# avr.net
KiCad netlist of a schematic drawn in Altium Designer
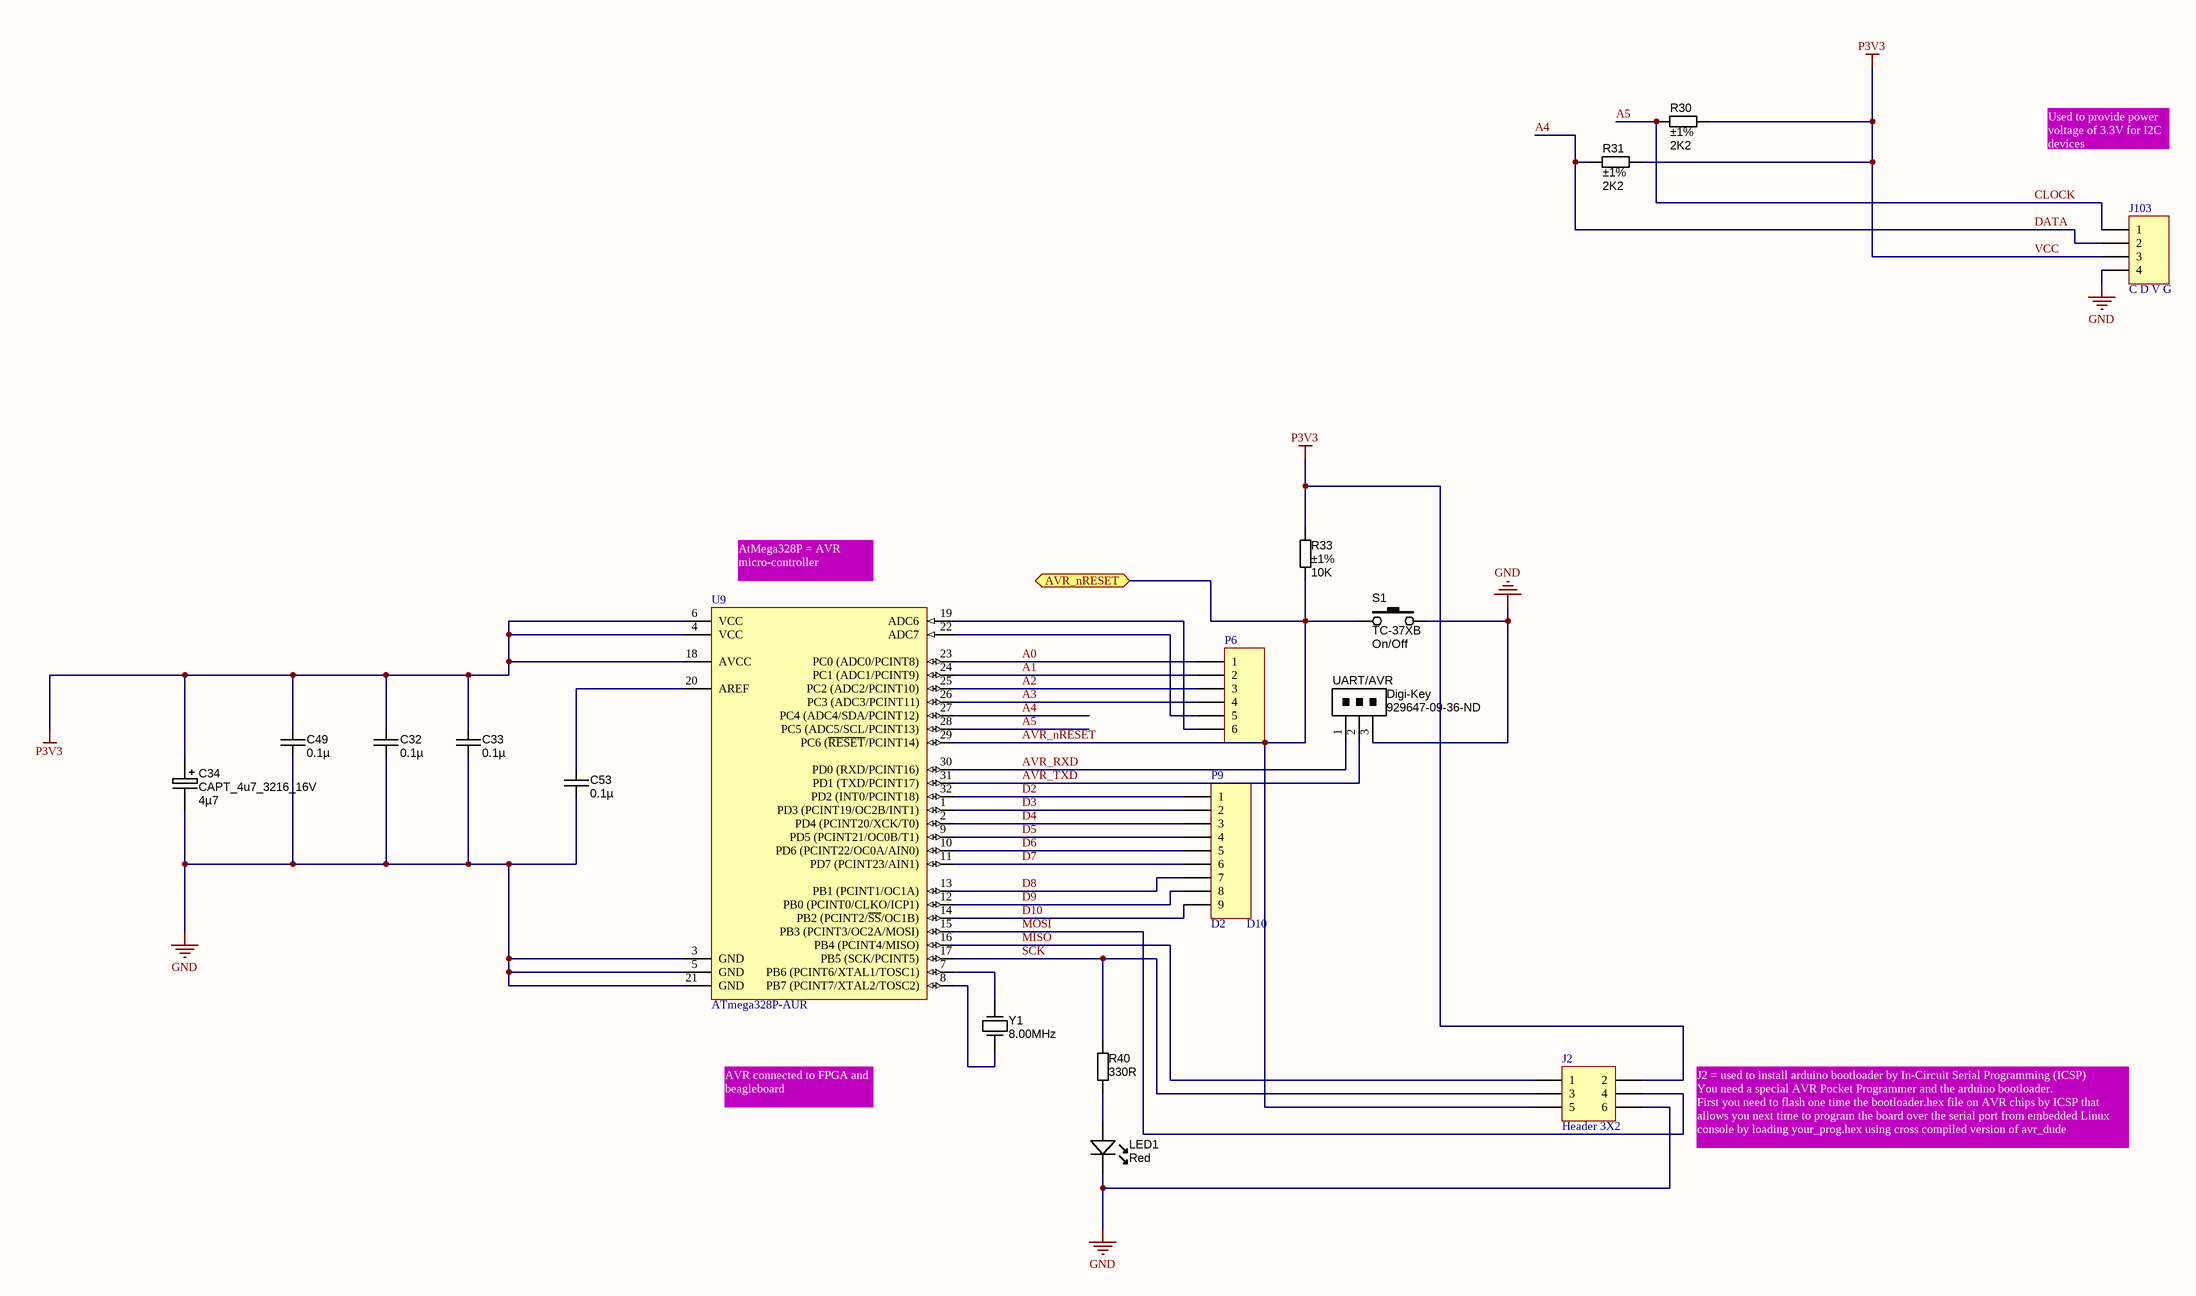
[diagram p0: avr.SchDoc]

(export (version "E")
  (design (tool "Eeschema 10.0.6"))
  (components
    (comp (ref "C32")
      (value "0.1µ")
      (footprint "CAPC1005X55N")
      (description "Capacitor SMD Cer 1uF 10% 16V X5R 0402")
      (fields (field (name "TOLERANCE") "±10%"))
      (libsource (lib "PBL - Capacitors") (part "CAPC_1u_0402_X5R_6V3_10%"))
    )
    (comp (ref "C33")
      (value "0.1µ")
      (footprint "CAPC1005X55N")
      (description "Capacitor SMD Cer 1uF 10% 16V X5R 0402")
      (fields (field (name "TOLERANCE") "±10%"))
      (libsource (lib "PBL - Capacitors") (part "CAPC_1u_0402_X5R_6V3_10%"))
    )
    (comp (ref "C34")
      (value "CAPT_4u7_3216_16V")
      (footprint "CAPMP3216X180N")
      (description "Capacitor SMD Tantalum 4.7uF 10% 16V 3216-18")
      (fields (field (name "ALTIUM_VALUE") "4µ7") (field (name "TOLERANCE") "±10%"))
      (libsource (lib "PBL - Capacitors") (part "CAPT_4u7_3216_16V"))
    )
    (comp (ref "C49")
      (value "0.1µ")
      (footprint "CAPC1005X55N")
      (description "Capacitor SMD Cer 1uF 10% 16V X5R 0402")
      (fields (field (name "TOLERANCE") "±10%"))
      (libsource (lib "PBL - Capacitors") (part "CAPC_1u_0402_X5R_6V3_10%"))
    )
    (comp (ref "C53")
      (value "0.1µ")
      (footprint "CAPC1005X55N")
      (description "Capacitor SMD Cer 1uF 10% 16V X5R 0402")
      (fields (field (name "TOLERANCE") "±10%"))
      (libsource (lib "PBL - Capacitors") (part "CAPC_1u_0402_X5R_6V3_10%"))
    )
    (comp (ref "J2")
      (value "Header 3X2")
      (footprint "HDR2X3")
      (description "Header, 3-Pin, Dual row")
      (fields (field (name "PUBLISHER") "Altium Limited"))
      (libsource (lib "Miscellaneous Connectors") (part "Header 3X2"))
    )
    (comp (ref "J103")
      (value "C D V G")
      (footprint "HDR1X4")
      (description "Header, 4-Pin")
      (fields (field (name "PUBLISHER") "Altium Limited"))
      (libsource (lib "Miscellaneous Connectors") (part "Header 4"))
    )
    (comp (ref "LED1")
      (value "~")
      (footprint "LED-0603-RED")
      (description "LED 0805 SMD Red 6mcd 621nm")
      (fields (field (name "COLOR") "Red"))
      (libsource (lib "PBL - Light Sources") (part "LED_SMD_Red_0805_6mcd"))
    )
    (comp (ref "P6")
      (value "~")
      (footprint "HDR1X6")
      (description "Header, 6-Pin")
      (fields (field (name "PUBLISHER") "Altium Limited"))
      (libsource (lib "Miscellaneous Connectors") (part "Header 6"))
    )
    (comp (ref "P9")
      (value "D2       D10")
      (footprint "HDR1X9")
      (description "Header, 9-Pin")
      (fields (field (name "PUBLISHER") "Altium Limited"))
      (libsource (lib "Miscellaneous Connectors") (part "Header 9"))
    )
    (comp (ref "R30")
      (value "2K2")
      (footprint "RESC1005N")
      (description "Resistor SMD chip 2.2k Ohm 0.125W 1% 0805")
      (fields (field (name "TOLERANCE") "±1%") (field (name "Comment") "Thick Film"))
      (libsource (lib "PBL - Resistors") (part "RES_2K2_0805_1%"))
    )
    (comp (ref "R31")
      (value "2K2")
      (footprint "RESC1005N")
      (description "Resistor SMD chip 2.2k Ohm 0.125W 1% 0805")
      (fields (field (name "TOLERANCE") "±1%") (field (name "Comment") "Thick Film"))
      (libsource (lib "PBL - Resistors") (part "RES_2K2_0805_1%"))
    )
    (comp (ref "R33")
      (value "10K")
      (footprint "RESC1005X40N")
      (description "Resistor SMD chip 10k Ohm 0.063W 1% 0402")
      (fields (field (name "TOLERANCE") "±1%") (field (name "Comment") "Thick Film"))
      (libsource (lib "PBL - Resistors") (part "RES_10K_0402_1%"))
    )
    (comp (ref "R40")
      (value "330R")
      (footprint "RESC1005X40N")
      (description "Resistor SMD chip 330 Ohm 0.063W 5% 0402")
      (fields (field (name "TOLERANCE") "±5%") (field (name "Comment") "Thick Film"))
      (libsource (lib "PBL - Resistors") (part "RES_330R_0402_5%"))
    )
    (comp (ref "S1")
      (value "SW_THT_PB_5.0mm")
      (footprint "TACT-SWITCH-TS1143")
      (description "Switch, tact, 5.0mm stem")
      (fields (field (name "MANUFACTURER PART NUMBER 1") "TC-37XB") (field (name "FUNCTION") "On/Off"))
      (libsource (lib "PBL - Switches") (part "SW_THT_PB_5.0mm"))
    )
    (comp (ref "U9")
      (value "ATmega328P-AUR")
      (footprint "32A_N")
      (fields (field (name "PUBLISHER") "Altium Limited"))
      (libsource (lib "Atmel Microcontroller 8-Bit megaAVR") (part "ATmega328-AUR"))
    )
    (comp (ref "UART/AVR")
      (value "R T G")
      (footprint "1x3POS_HEADER")
      (description "Pin Header, THT, Single-row, 2.54mm pitch")
      (fields
        (field (name "SUPPLIER 1") "Digi-Key")
        (field (name "SUPPLIER PART NUMBER 1") "929647-09-36-ND")
      )
      (libsource (lib "PBL - Connectors") (part "CONN_HEADER_1x3P_0.100in"))
    )
    (comp (ref "Y1")
      (value "8.00MHz")
      (footprint "CRYSTAL_HC49-US-SM")
      (description "Resonator Ceramic 8.00 MHz 30ppm")
      (libsource (lib "PBL - Resonators") (part "Crystal_6MHz_HC49/US"))
    )
  )
  (nets
    (net (code "1") (name "/A0") (class "Default")
      (node (ref "P6") (pin "1") (pinfunction "1_1") (pintype "passive"))
      (node (ref "U9") (pin "23") (pinfunction "PC0_(ADC0/PCINT8)_23") (pintype "bidirectional"))
    )
    (net (code "2") (name "/A1") (class "Default")
      (node (ref "P6") (pin "2") (pinfunction "2_2") (pintype "passive"))
      (node (ref "U9") (pin "24") (pinfunction "PC1_(ADC1/PCINT9)_24") (pintype "bidirectional"))
    )
    (net (code "3") (name "/A2") (class "Default")
      (node (ref "P6") (pin "3") (pinfunction "3_3") (pintype "passive"))
      (node (ref "U9") (pin "25") (pinfunction "PC2_(ADC2/PCINT10)_25") (pintype "bidirectional"))
    )
    (net (code "4") (name "/A3") (class "Default")
      (node (ref "P6") (pin "4") (pinfunction "4_4") (pintype "passive"))
      (node (ref "U9") (pin "26") (pinfunction "PC3_(ADC3/PCINT11)_26") (pintype "bidirectional"))
    )
    (net (code "5") (name "/A4") (class "Default")
      (node (ref "J103") (pin "2") (pinfunction "2_2") (pintype "passive"))
      (node (ref "R31") (pin "1") (pinfunction "1_1") (pintype "passive"))
      (node (ref "U9") (pin "27") (pinfunction "PC4_(ADC4/SDA/PCINT12)_27") (pintype "bidirectional"))
    )
    (net (code "6") (name "/A5") (class "Default")
      (node (ref "J103") (pin "1") (pinfunction "1_1") (pintype "passive"))
      (node (ref "R30") (pin "1") (pinfunction "1_1") (pintype "passive"))
      (node (ref "U9") (pin "28") (pinfunction "PC5_(ADC5/SCL/PCINT13)_28") (pintype "bidirectional"))
    )
    (net (code "7") (name "/AVR_RXD") (class "Default")
      (node (ref "U9") (pin "30") (pinfunction "PD0_(RXD/PCINT16)_30") (pintype "bidirectional"))
      (node (ref "UART/AVR") (pin "1") (pinfunction "1_1") (pintype "passive"))
    )
    (net (code "8") (name "/AVR_TXD") (class "Default")
      (node (ref "U9") (pin "31") (pinfunction "PD1_(TXD/PCINT17)_31") (pintype "bidirectional"))
      (node (ref "UART/AVR") (pin "2") (pinfunction "2_2") (pintype "passive"))
    )
    (net (code "9") (name "/AVR_nRESET") (class "Default")
      (node (ref "J2") (pin "5") (pinfunction "5_5") (pintype "passive"))
      (node (ref "R33") (pin "2") (pinfunction "2_2") (pintype "passive"))
      (node (ref "S1") (pin "1") (pintype "passive"))
      (node (ref "U9") (pin "29") (pinfunction "PC6_(~{RESET}/PCINT14)_29") (pintype "bidirectional"))
    )
    (net (code "10") (name "/D2") (class "Default")
      (node (ref "P9") (pin "1") (pinfunction "1_1") (pintype "passive"))
      (node (ref "U9") (pin "32") (pinfunction "PD2_(INT0/PCINT18)_32") (pintype "bidirectional"))
    )
    (net (code "11") (name "/D3") (class "Default")
      (node (ref "P9") (pin "2") (pinfunction "2_2") (pintype "passive"))
      (node (ref "U9") (pin "1") (pinfunction "PD3_(PCINT19/OC2B/INT1)_1") (pintype "bidirectional"))
    )
    (net (code "12") (name "/D4") (class "Default")
      (node (ref "P9") (pin "3") (pinfunction "3_3") (pintype "passive"))
      (node (ref "U9") (pin "2") (pinfunction "PD4_(PCINT20/XCK/T0)_2") (pintype "bidirectional"))
    )
    (net (code "13") (name "/D5") (class "Default")
      (node (ref "P9") (pin "4") (pinfunction "4_4") (pintype "passive"))
      (node (ref "U9") (pin "9") (pinfunction "PD5_(PCINT21/OC0B/T1)_9") (pintype "bidirectional"))
    )
    (net (code "14") (name "/D6") (class "Default")
      (node (ref "P9") (pin "5") (pinfunction "5_5") (pintype "passive"))
      (node (ref "U9") (pin "10") (pinfunction "PD6_(PCINT22/OC0A/AIN0)_10") (pintype "bidirectional"))
    )
    (net (code "15") (name "/D7") (class "Default")
      (node (ref "P9") (pin "6") (pinfunction "6_6") (pintype "passive"))
      (node (ref "U9") (pin "11") (pinfunction "PD7_(PCINT23/AIN1)_11") (pintype "bidirectional"))
    )
    (net (code "16") (name "/D8") (class "Default")
      (node (ref "P9") (pin "7") (pinfunction "7_7") (pintype "passive"))
      (node (ref "U9") (pin "13") (pinfunction "PB1_(PCINT1/OC1A)_13") (pintype "bidirectional"))
    )
    (net (code "17") (name "/D9") (class "Default")
      (node (ref "P9") (pin "8") (pinfunction "8_8") (pintype "passive"))
      (node (ref "U9") (pin "12") (pinfunction "PB0_(PCINT0/CLKO/ICP1)_12") (pintype "bidirectional"))
    )
    (net (code "18") (name "/D10") (class "Default")
      (node (ref "P9") (pin "9") (pinfunction "9_9") (pintype "passive"))
      (node (ref "U9") (pin "14") (pinfunction "PB2_(PCINT2/~{SS}/OC1B)_14") (pintype "bidirectional"))
    )
    (net (code "19") (name "/MISO") (class "Default")
      (node (ref "J2") (pin "1") (pinfunction "1_1") (pintype "passive"))
      (node (ref "U9") (pin "16") (pinfunction "PB4_(PCINT4/MISO)_16") (pintype "bidirectional"))
    )
    (net (code "20") (name "/MOSI") (class "Default")
      (node (ref "J2") (pin "4") (pinfunction "4_4") (pintype "passive"))
      (node (ref "U9") (pin "15") (pinfunction "PB3_(PCINT3/OC2A/MOSI)_15") (pintype "bidirectional"))
    )
    (net (code "21") (name "/SCK") (class "Default")
      (node (ref "J2") (pin "3") (pinfunction "3_3") (pintype "passive"))
      (node (ref "R40") (pin "1") (pinfunction "1_1") (pintype "passive"))
      (node (ref "U9") (pin "17") (pinfunction "PB5_(SCK/PCINT5)_17") (pintype "bidirectional"))
    )
    (net (code "22") (name "GND") (class "Default")
      (node (ref "C32") (pin "2") (pintype "passive"))
      (node (ref "C33") (pin "2") (pintype "passive"))
      (node (ref "C34") (pin "2") (pintype "passive"))
      (node (ref "C49") (pin "2") (pintype "passive"))
      (node (ref "C53") (pin "2") (pintype "passive"))
      (node (ref "J103") (pin "4") (pinfunction "4_4") (pintype "passive"))
      (node (ref "J2") (pin "6") (pinfunction "6_6") (pintype "passive"))
      (node (ref "LED1") (pin "K") (pinfunction "K_K") (pintype "passive"))
      (node (ref "S1") (pin "2") (pintype "passive"))
      (node (ref "U9") (pin "21") (pinfunction "GND_21") (pintype "power_in"))
      (node (ref "U9") (pin "3") (pinfunction "GND_3") (pintype "power_in"))
      (node (ref "U9") (pin "5") (pinfunction "GND_5") (pintype "power_in"))
      (node (ref "UART/AVR") (pin "3") (pinfunction "3_3") (pintype "passive"))
    )
    (net (code "23") (name "Net-(LED1-PadA)") (class "Default")
      (node (ref "LED1") (pin "A") (pinfunction "A_A") (pintype "passive"))
      (node (ref "R40") (pin "2") (pinfunction "2_2") (pintype "passive"))
    )
    (net (code "24") (name "Net-(U9-ADC6)") (class "Default")
      (node (ref "P6") (pin "6") (pinfunction "6_6") (pintype "passive"))
      (node (ref "U9") (pin "19") (pinfunction "ADC6_19") (pintype "input"))
    )
    (net (code "25") (name "Net-(U9-ADC7)") (class "Default")
      (node (ref "P6") (pin "5") (pinfunction "5_5") (pintype "passive"))
      (node (ref "U9") (pin "22") (pinfunction "ADC7_22") (pintype "input"))
    )
    (net (code "26") (name "Net-(U9-AREF)") (class "Default")
      (node (ref "C53") (pin "1") (pintype "passive"))
      (node (ref "U9") (pin "20") (pinfunction "AREF_20") (pintype "passive"))
    )
    (net (code "27") (name "Net-(U9-PB6_(PCINT6{slash}XTAL1{slash}TOSC1))") (class "Default")
      (node (ref "U9") (pin "7") (pinfunction "PB6_(PCINT6/XTAL1/TOSC1)_7") (pintype "bidirectional"))
      (node (ref "Y1") (pin "2") (pinfunction "OUT_2") (pintype "passive"))
    )
    (net (code "28") (name "Net-(U9-PB7_(PCINT7{slash}XTAL2{slash}TOSC2))") (class "Default")
      (node (ref "U9") (pin "8") (pinfunction "PB7_(PCINT7/XTAL2/TOSC2)_8") (pintype "bidirectional"))
      (node (ref "Y1") (pin "1") (pinfunction "IN_1") (pintype "passive"))
    )
    (net (code "29") (name "P3V3") (class "Default")
      (node (ref "C32") (pin "1") (pintype "passive"))
      (node (ref "C33") (pin "1") (pintype "passive"))
      (node (ref "C34") (pin "1") (pintype "passive"))
      (node (ref "C49") (pin "1") (pintype "passive"))
      (node (ref "J103") (pin "3") (pinfunction "3_3") (pintype "passive"))
      (node (ref "J2") (pin "2") (pinfunction "2_2") (pintype "passive"))
      (node (ref "R30") (pin "2") (pinfunction "2_2") (pintype "passive"))
      (node (ref "R31") (pin "2") (pinfunction "2_2") (pintype "passive"))
      (node (ref "R33") (pin "1") (pinfunction "1_1") (pintype "passive"))
      (node (ref "U9") (pin "18") (pinfunction "AVCC_18") (pintype "power_in"))
      (node (ref "U9") (pin "4") (pinfunction "VCC_4") (pintype "power_in"))
      (node (ref "U9") (pin "6") (pinfunction "VCC_6") (pintype "power_in"))
    )
  )
)
